# part_1_2020-12-24_12-20-03.net
KiCad netlist of a schematic drawn in Altium Designer
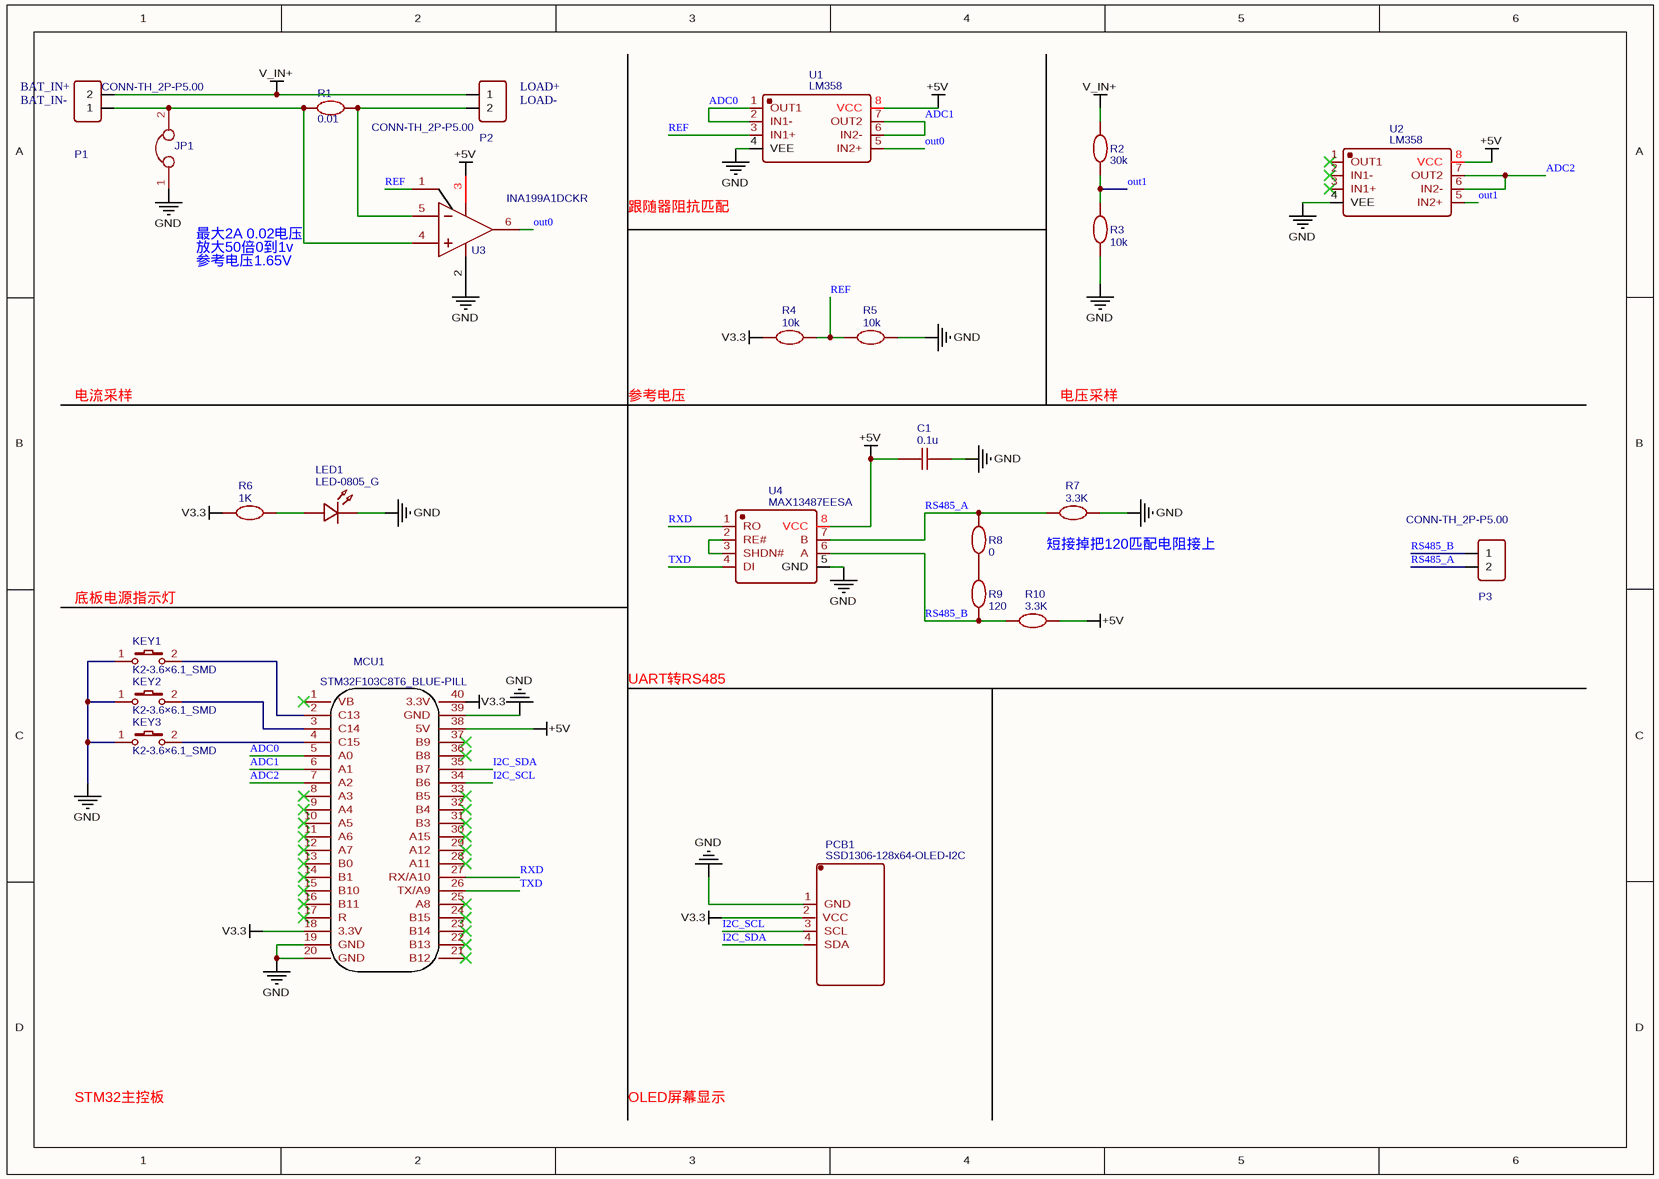
[diagram p0: part_1_2020-12-24_12-20-03.schdoc]

(export (version "E")
  (design (tool "Eeschema 10.0.6"))
  (components
    (comp (ref "C1")
      (value "0.1u")
      (footprint "C0805")
      (fields (field (name "CONTRIBUTOR") "LCEDA_Lib"))
      (libsource (lib "altium-import") (part "root_2_0.1u_"))
    )
    (comp (ref "JP1")
      (value "JUMPER")
      (footprint "HDR-F-2.54_1X2")
      (libsource (lib "altium-import") (part "root_1_JUMPER_"))
    )
    (comp (ref "KEY1")
      (value "K2-3.6×6.1_SMD")
      (footprint "KEY-SMD_2P-L6.2-W3.6-LS8.0")
      (fields
        (field (name "BOM_SUPPLIER PART") "C118141")
        (field (name "BOM_MANUFACTURER PART") "K2-1107ST-A4SW-06")
        (field (name "CONTRIBUTOR") "LCEDA_Lib")
      )
      (libsource (lib "PCB_Project") (part "K2-3.6×6.1_SMD"))
    )
    (comp (ref "KEY2")
      (value "K2-3.6×6.1_SMD")
      (footprint "KEY-SMD_2P-L6.2-W3.6-LS8.0")
      (fields
        (field (name "BOM_SUPPLIER PART") "C118141")
        (field (name "BOM_MANUFACTURER PART") "K2-1107ST-A4SW-06")
        (field (name "CONTRIBUTOR") "LCEDA_Lib")
      )
      (libsource (lib "PCB_Project") (part "K2-3.6×6.1_SMD"))
    )
    (comp (ref "KEY3")
      (value "K2-3.6×6.1_SMD")
      (footprint "KEY-SMD_2P-L6.2-W3.6-LS8.0")
      (fields
        (field (name "BOM_SUPPLIER PART") "C118141")
        (field (name "BOM_MANUFACTURER PART") "K2-1107ST-A4SW-06")
        (field (name "CONTRIBUTOR") "LCEDA_Lib")
      )
      (libsource (lib "PCB_Project") (part "K2-3.6×6.1_SMD"))
    )
    (comp (ref "LED1")
      (value "LED-0805_G")
      (footprint "LED0805_GREEN")
      (fields
        (field (name "BOM_MANUFACTURER PART") "19-217/GHC-YR1S2/3T")
        (field (name "BOM_SUPPLIER PART") "C72043")
        (field (name "CONTRIBUTOR") "LCEDA_Lib")
      )
      (libsource (lib "altium-import") (part "root_0_LED-0805_G_"))
    )
    (comp (ref "MCU1")
      (value "STM32F103C8T6_BLUE-PILL")
      (footprint "STM32F103C8T6_BLUE-PILL")
      (fields (field (name "CONTRIBUTOR") "lzbsuzhou"))
      (libsource (lib "altium-import") (part "root_0_STM32F103C8T6_BLUE-PILL_"))
    )
    (comp (ref "P1")
      (value "CONN-TH_2P-P5.00")
      (footprint "CONN-TH_2P-P5.00")
      (fields (field (name "CONTRIBUTOR") "LCEDA_Lib"))
      (libsource (lib "altium-import") (part "root_2_CONN-TH_2P-P5.00_"))
    )
    (comp (ref "P2")
      (value "CONN-TH_2P-P5.00")
      (footprint "CONN-TH_2P-P5.00")
      (fields (field (name "CONTRIBUTOR") "LCEDA_Lib"))
      (libsource (lib "altium-import") (part "root_0_CONN-TH_2P-P5.00_"))
    )
    (comp (ref "P3")
      (value "CONN-TH_2P-P5.00")
      (footprint "CONN-TH_2P-P5.00")
      (fields (field (name "CONTRIBUTOR") "LCEDA_Lib"))
      (libsource (lib "altium-import") (part "root_0_CONN-TH_2P-P5.00_"))
    )
    (comp (ref "PCB1")
      (value "SSD1306-128x64-OLED-I2C")
      (footprint "SSD1306_GNDVCC")
      (libsource (lib "altium-import") (part "root_0_SSD1306-128x64-OLED-I2C_"))
    )
    (comp (ref "R1")
      (value "0.01")
      (footprint "R2512")
      (fields (field (name "CONTRIBUTOR") "LCEDA_Lib"))
      (libsource (lib "altium-import") (part "root_2_0.01_"))
    )
    (comp (ref "R2")
      (value "30k")
      (footprint "C0805")
      (fields (field (name "CONTRIBUTOR") "LCEDA_Lib"))
      (libsource (lib "altium-import") (part "root_1_3k_"))
    )
    (comp (ref "R3")
      (value "10k")
      (footprint "C0805")
      (fields (field (name "CONTRIBUTOR") "LCEDA_Lib"))
      (libsource (lib "altium-import") (part "root_1_1k_"))
    )
    (comp (ref "R4")
      (value "10k")
      (footprint "C0805")
      (fields (field (name "CONTRIBUTOR") "LCEDA_Lib"))
      (libsource (lib "altium-import") (part "root_2_10k_"))
    )
    (comp (ref "R5")
      (value "10k")
      (footprint "C0805")
      (fields (field (name "CONTRIBUTOR") "LCEDA_Lib"))
      (libsource (lib "altium-import") (part "root_2_10k_"))
    )
    (comp (ref "R6")
      (value "1K")
      (footprint "R0805")
      (fields (field (name "CONTRIBUTOR") "LCEDA_Lib"))
      (libsource (lib "altium-import") (part "root_2_1K_"))
    )
    (comp (ref "R7")
      (value "3.3K")
      (footprint "R0805")
      (fields (field (name "CONTRIBUTOR") "LCEDA_Lib"))
      (libsource (lib "altium-import") (part "root_2_3.3K_"))
    )
    (comp (ref "R8")
      (value "0")
      (footprint "R0805")
      (fields (field (name "CONTRIBUTOR") "LCEDA_Lib"))
      (libsource (lib "altium-import") (part "root_1_0_"))
    )
    (comp (ref "R9")
      (value "120")
      (footprint "R0805")
      (fields (field (name "CONTRIBUTOR") "LCEDA_Lib"))
      (libsource (lib "altium-import") (part "root_1_120_"))
    )
    (comp (ref "R10")
      (value "3.3K")
      (footprint "R0805")
      (fields (field (name "CONTRIBUTOR") "LCEDA_Lib"))
      (libsource (lib "altium-import") (part "root_0_3.3K_"))
    )
    (comp (ref "U1")
      (value "LM358")
      (footprint "SOP-8_L4.9-W3.9-P1.27-LS6.0-BL")
      (fields (field (name "BOM_SUPPLIER PART") "C328566") (field (name "CONTRIBUTOR") "LCSC"))
      (libsource (lib "altium-import") (part "root_0_LM358_"))
    )
    (comp (ref "U2")
      (value "LM358")
      (footprint "SOP-8_L4.9-W3.9-P1.27-LS6.0-BL")
      (fields (field (name "BOM_SUPPLIER PART") "C328566") (field (name "CONTRIBUTOR") "LCSC"))
      (libsource (lib "altium-import") (part "root_0_LM358_"))
    )
    (comp (ref "U3")
      (value "INA199A1DCKR")
      (footprint "SOT-363_L2.0-W1.3-P0.65-LS2.1-BR")
      (fields
        (field (name "BOM_SUPPLIER PART") "C132098")
        (field (name "BOM_MANUFACTURER PART") "INA199A3DCKR")
        (field (name "CONTRIBUTOR") "LCSC")
      )
      (libsource (lib "altium-import") (part "root_0_INA199A1DCKR_"))
    )
    (comp (ref "U4")
      (value "MAX13487EESA")
      (footprint "SOIC-8_L4.9-W3.9-P1.27-LS6.0-BL")
      (fields (field (name "BOM_SUPPLIER PART") "C18347"))
      (libsource (lib "altium-import") (part "root_0_MAX13487EESA_"))
    )
  )
  (nets
    (net (code "1") (name "+5V") (class "Default")
      (node (ref "C1") (pin "2") (pinfunction "2_2") (pintype "passive"))
      (node (ref "MCU1") (pin "38") (pinfunction "5V_38") (pintype "passive"))
      (node (ref "R10") (pin "2") (pinfunction "2_2") (pintype "passive"))
      (node (ref "U1") (pin "8") (pinfunction "VCC_8") (pintype "passive"))
      (node (ref "U2") (pin "8") (pinfunction "VCC_8") (pintype "passive"))
      (node (ref "U3") (pin "3") (pinfunction "V+_3") (pintype "passive"))
      (node (ref "U4") (pin "8") (pinfunction "VCC_8") (pintype "passive"))
    )
    (net (code "2") (name "/ADC0") (class "Default")
      (node (ref "MCU1") (pin "5") (pinfunction "A0_5") (pintype "passive"))
      (node (ref "U1") (pin "1") (pinfunction "OUT1_1") (pintype "passive"))
      (node (ref "U1") (pin "2") (pinfunction "IN1-_2") (pintype "passive"))
    )
    (net (code "3") (name "/ADC1") (class "Default")
      (node (ref "MCU1") (pin "6") (pinfunction "A1_6") (pintype "passive"))
      (node (ref "U1") (pin "6") (pinfunction "IN2-_6") (pintype "passive"))
      (node (ref "U1") (pin "7") (pinfunction "OUT2_7") (pintype "passive"))
    )
    (net (code "4") (name "/ADC2") (class "Default")
      (node (ref "MCU1") (pin "7") (pinfunction "A2_7") (pintype "passive"))
      (node (ref "U2") (pin "6") (pinfunction "IN2-_6") (pintype "passive"))
      (node (ref "U2") (pin "7") (pinfunction "OUT2_7") (pintype "passive"))
    )
    (net (code "5") (name "/I2C_SCL") (class "Default")
      (node (ref "MCU1") (pin "34") (pinfunction "B6_34") (pintype "passive"))
      (node (ref "PCB1") (pin "3") (pinfunction "SCL_3") (pintype "passive"))
    )
    (net (code "6") (name "/I2C_SDA") (class "Default")
      (node (ref "MCU1") (pin "35") (pinfunction "B7_35") (pintype "passive"))
      (node (ref "PCB1") (pin "4") (pinfunction "SDA_4") (pintype "passive"))
    )
    (net (code "7") (name "/REF") (class "Default")
      (node (ref "R4") (pin "1") (pinfunction "1_1") (pintype "passive"))
      (node (ref "R5") (pin "2") (pinfunction "2_2") (pintype "passive"))
      (node (ref "U1") (pin "3") (pinfunction "IN1+_3") (pintype "passive"))
      (node (ref "U3") (pin "1") (pinfunction "REF_1") (pintype "passive"))
    )
    (net (code "8") (name "/RS485_A") (class "Default")
      (node (ref "P3") (pin "2") (pinfunction "2_2") (pintype "passive"))
      (node (ref "R7") (pin "2") (pinfunction "2_2") (pintype "passive"))
      (node (ref "R8") (pin "2") (pinfunction "2_2") (pintype "passive"))
      (node (ref "U4") (pin "7") (pinfunction "B_7") (pintype "passive"))
    )
    (net (code "9") (name "/RS485_B") (class "Default")
      (node (ref "P3") (pin "1") (pinfunction "1_1") (pintype "passive"))
      (node (ref "R10") (pin "1") (pinfunction "1_1") (pintype "passive"))
      (node (ref "R9") (pin "1") (pinfunction "1_1") (pintype "passive"))
      (node (ref "U4") (pin "6") (pinfunction "A_6") (pintype "passive"))
    )
    (net (code "10") (name "/RXD") (class "Default")
      (node (ref "MCU1") (pin "27") (pinfunction "RX/A10_27") (pintype "passive"))
      (node (ref "U4") (pin "1") (pinfunction "RO_1") (pintype "passive"))
    )
    (net (code "11") (name "/TXD") (class "Default")
      (node (ref "MCU1") (pin "26") (pinfunction "TX/A9_26") (pintype "passive"))
      (node (ref "U4") (pin "4") (pinfunction "DI_4") (pintype "passive"))
    )
    (net (code "12") (name "/out0") (class "Default")
      (node (ref "U1") (pin "5") (pinfunction "IN2+_5") (pintype "passive"))
      (node (ref "U3") (pin "6") (pinfunction "OUT_6") (pintype "passive"))
    )
    (net (code "13") (name "/out1") (class "Default")
      (node (ref "R2") (pin "1") (pinfunction "1_1") (pintype "passive"))
      (node (ref "R3") (pin "2") (pinfunction "2_2") (pintype "passive"))
      (node (ref "U2") (pin "5") (pinfunction "IN2+_5") (pintype "passive"))
    )
    (net (code "14") (name "GND") (class "Default")
      (node (ref "C1") (pin "1") (pinfunction "1_1") (pintype "passive"))
      (node (ref "JP1") (pin "1") (pinfunction "1_1") (pintype "passive"))
      (node (ref "KEY1") (pin "1") (pinfunction "1_1") (pintype "passive"))
      (node (ref "KEY2") (pin "1") (pinfunction "1_1") (pintype "passive"))
      (node (ref "KEY3") (pin "1") (pinfunction "1_1") (pintype "passive"))
      (node (ref "LED1") (pin "2") (pinfunction "2_2") (pintype "passive"))
      (node (ref "MCU1") (pin "19") (pinfunction "GND_19") (pintype "passive"))
      (node (ref "MCU1") (pin "20") (pinfunction "GND_20") (pintype "passive"))
      (node (ref "MCU1") (pin "39") (pinfunction "GND_39") (pintype "passive"))
      (node (ref "PCB1") (pin "1") (pinfunction "GND_1") (pintype "passive"))
      (node (ref "R3") (pin "1") (pinfunction "1_1") (pintype "passive"))
      (node (ref "R5") (pin "1") (pinfunction "1_1") (pintype "passive"))
      (node (ref "R7") (pin "1") (pinfunction "1_1") (pintype "passive"))
      (node (ref "U1") (pin "4") (pinfunction "VEE_4") (pintype "passive"))
      (node (ref "U2") (pin "4") (pinfunction "VEE_4") (pintype "passive"))
      (node (ref "U3") (pin "2") (pinfunction "GND_2") (pintype "passive"))
      (node (ref "U4") (pin "5") (pinfunction "GND_5") (pintype "passive"))
    )
    (net (code "15") (name "Net-(LED1-Pad1)") (class "Default")
      (node (ref "LED1") (pin "1") (pinfunction "1_1") (pintype "passive"))
      (node (ref "R6") (pin "1") (pinfunction "1_1") (pintype "passive"))
    )
    (net (code "16") (name "Net-(MCU1-C13)") (class "Default")
      (node (ref "KEY1") (pin "2") (pinfunction "2_2") (pintype "passive"))
      (node (ref "MCU1") (pin "2") (pinfunction "C13_2") (pintype "passive"))
    )
    (net (code "17") (name "Net-(MCU1-C14)") (class "Default")
      (node (ref "KEY2") (pin "2") (pinfunction "2_2") (pintype "passive"))
      (node (ref "MCU1") (pin "3") (pinfunction "C14_3") (pintype "passive"))
    )
    (net (code "18") (name "Net-(MCU1-C15)") (class "Default")
      (node (ref "KEY3") (pin "2") (pinfunction "2_2") (pintype "passive"))
      (node (ref "MCU1") (pin "4") (pinfunction "C15_4") (pintype "passive"))
    )
    (net (code "19") (name "Net-(R8-Pad1)") (class "Default")
      (node (ref "R8") (pin "1") (pinfunction "1_1") (pintype "passive"))
      (node (ref "R9") (pin "2") (pinfunction "2_2") (pintype "passive"))
    )
    (net (code "20") (name "Net-(U3-IN+)") (class "Default")
      (node (ref "JP1") (pin "2") (pinfunction "2_2") (pintype "passive"))
      (node (ref "P1") (pin "1") (pinfunction "1_1") (pintype "passive"))
      (node (ref "R1") (pin "2") (pinfunction "2_2") (pintype "passive"))
      (node (ref "U3") (pin "4") (pinfunction "IN+_4") (pintype "passive"))
    )
    (net (code "21") (name "Net-(U3-IN-)") (class "Default")
      (node (ref "P2") (pin "2") (pinfunction "2_2") (pintype "passive"))
      (node (ref "R1") (pin "1") (pinfunction "1_1") (pintype "passive"))
      (node (ref "U3") (pin "5") (pinfunction "IN-_5") (pintype "passive"))
    )
    (net (code "22") (name "Net-(U4-RE#)") (class "Default")
      (node (ref "U4") (pin "2") (pinfunction "RE#_2") (pintype "passive"))
      (node (ref "U4") (pin "3") (pinfunction "SHDN#_3") (pintype "passive"))
    )
    (net (code "23") (name "V3.3") (class "Default")
      (node (ref "MCU1") (pin "18") (pinfunction "3.3V_18") (pintype "passive"))
      (node (ref "MCU1") (pin "40") (pinfunction "3.3V_40") (pintype "passive"))
      (node (ref "PCB1") (pin "2") (pinfunction "VCC_2") (pintype "passive"))
      (node (ref "R4") (pin "2") (pinfunction "2_2") (pintype "passive"))
      (node (ref "R6") (pin "2") (pinfunction "2_2") (pintype "passive"))
    )
    (net (code "24") (name "V_IN+") (class "Default")
      (node (ref "P1") (pin "2") (pinfunction "2_2") (pintype "passive"))
      (node (ref "P2") (pin "1") (pinfunction "1_1") (pintype "passive"))
      (node (ref "R2") (pin "2") (pinfunction "2_2") (pintype "passive"))
    )
    (net (code "25") (name "unconnected-(MCU1-A3-Pad8)") (class "Default")
      (node (ref "MCU1") (pin "8") (pinfunction "A3_8") (pintype "passive+no_connect"))
    )
    (net (code "26") (name "unconnected-(MCU1-A4-Pad9)") (class "Default")
      (node (ref "MCU1") (pin "9") (pinfunction "A4_9") (pintype "passive+no_connect"))
    )
    (net (code "27") (name "unconnected-(MCU1-A5-Pad10)") (class "Default")
      (node (ref "MCU1") (pin "10") (pinfunction "A5_10") (pintype "passive+no_connect"))
    )
    (net (code "28") (name "unconnected-(MCU1-A6-Pad11)") (class "Default")
      (node (ref "MCU1") (pin "11") (pinfunction "A6_11") (pintype "passive+no_connect"))
    )
    (net (code "29") (name "unconnected-(MCU1-A7-Pad12)") (class "Default")
      (node (ref "MCU1") (pin "12") (pinfunction "A7_12") (pintype "passive+no_connect"))
    )
    (net (code "30") (name "unconnected-(MCU1-A8-Pad25)") (class "Default")
      (node (ref "MCU1") (pin "25") (pinfunction "A8_25") (pintype "passive+no_connect"))
    )
    (net (code "31") (name "unconnected-(MCU1-A11-Pad28)") (class "Default")
      (node (ref "MCU1") (pin "28") (pinfunction "A11_28") (pintype "passive+no_connect"))
    )
    (net (code "32") (name "unconnected-(MCU1-A12-Pad29)") (class "Default")
      (node (ref "MCU1") (pin "29") (pinfunction "A12_29") (pintype "passive+no_connect"))
    )
    (net (code "33") (name "unconnected-(MCU1-A15-Pad30)") (class "Default")
      (node (ref "MCU1") (pin "30") (pinfunction "A15_30") (pintype "passive+no_connect"))
    )
    (net (code "34") (name "unconnected-(MCU1-B0-Pad13)") (class "Default")
      (node (ref "MCU1") (pin "13") (pinfunction "B0_13") (pintype "passive+no_connect"))
    )
    (net (code "35") (name "unconnected-(MCU1-B1-Pad14)") (class "Default")
      (node (ref "MCU1") (pin "14") (pinfunction "B1_14") (pintype "passive+no_connect"))
    )
    (net (code "36") (name "unconnected-(MCU1-B3-Pad31)") (class "Default")
      (node (ref "MCU1") (pin "31") (pinfunction "B3_31") (pintype "passive+no_connect"))
    )
    (net (code "37") (name "unconnected-(MCU1-B4-Pad32)") (class "Default")
      (node (ref "MCU1") (pin "32") (pinfunction "B4_32") (pintype "passive+no_connect"))
    )
    (net (code "38") (name "unconnected-(MCU1-B5-Pad33)") (class "Default")
      (node (ref "MCU1") (pin "33") (pinfunction "B5_33") (pintype "passive+no_connect"))
    )
    (net (code "39") (name "unconnected-(MCU1-B8-Pad36)") (class "Default")
      (node (ref "MCU1") (pin "36") (pinfunction "B8_36") (pintype "passive+no_connect"))
    )
    (net (code "40") (name "unconnected-(MCU1-B9-Pad37)") (class "Default")
      (node (ref "MCU1") (pin "37") (pinfunction "B9_37") (pintype "passive+no_connect"))
    )
    (net (code "41") (name "unconnected-(MCU1-B10-Pad15)") (class "Default")
      (node (ref "MCU1") (pin "15") (pinfunction "B10_15") (pintype "passive+no_connect"))
    )
    (net (code "42") (name "unconnected-(MCU1-B11-Pad16)") (class "Default")
      (node (ref "MCU1") (pin "16") (pinfunction "B11_16") (pintype "passive+no_connect"))
    )
    (net (code "43") (name "unconnected-(MCU1-B12-Pad21)") (class "Default")
      (node (ref "MCU1") (pin "21") (pinfunction "B12_21") (pintype "passive+no_connect"))
    )
    (net (code "44") (name "unconnected-(MCU1-B13-Pad22)") (class "Default")
      (node (ref "MCU1") (pin "22") (pinfunction "B13_22") (pintype "passive+no_connect"))
    )
    (net (code "45") (name "unconnected-(MCU1-B14-Pad23)") (class "Default")
      (node (ref "MCU1") (pin "23") (pinfunction "B14_23") (pintype "passive+no_connect"))
    )
    (net (code "46") (name "unconnected-(MCU1-B15-Pad24)") (class "Default")
      (node (ref "MCU1") (pin "24") (pinfunction "B15_24") (pintype "passive+no_connect"))
    )
    (net (code "47") (name "unconnected-(MCU1-R-Pad17)") (class "Default")
      (node (ref "MCU1") (pin "17") (pinfunction "R_17") (pintype "passive+no_connect"))
    )
    (net (code "48") (name "unconnected-(MCU1-VB-Pad1)") (class "Default")
      (node (ref "MCU1") (pin "1") (pinfunction "VB_1") (pintype "passive+no_connect"))
    )
    (net (code "49") (name "unconnected-(U2-IN1+-Pad3)") (class "Default")
      (node (ref "U2") (pin "3") (pinfunction "IN1+_3") (pintype "passive+no_connect"))
    )
    (net (code "50") (name "unconnected-(U2-IN1--Pad2)") (class "Default")
      (node (ref "U2") (pin "2") (pinfunction "IN1-_2") (pintype "passive+no_connect"))
    )
    (net (code "51") (name "unconnected-(U2-OUT1-Pad1)") (class "Default")
      (node (ref "U2") (pin "1") (pinfunction "OUT1_1") (pintype "passive+no_connect"))
    )
  )
)
